# Main.net
KiCad netlist of a schematic drawn in Altium Designer
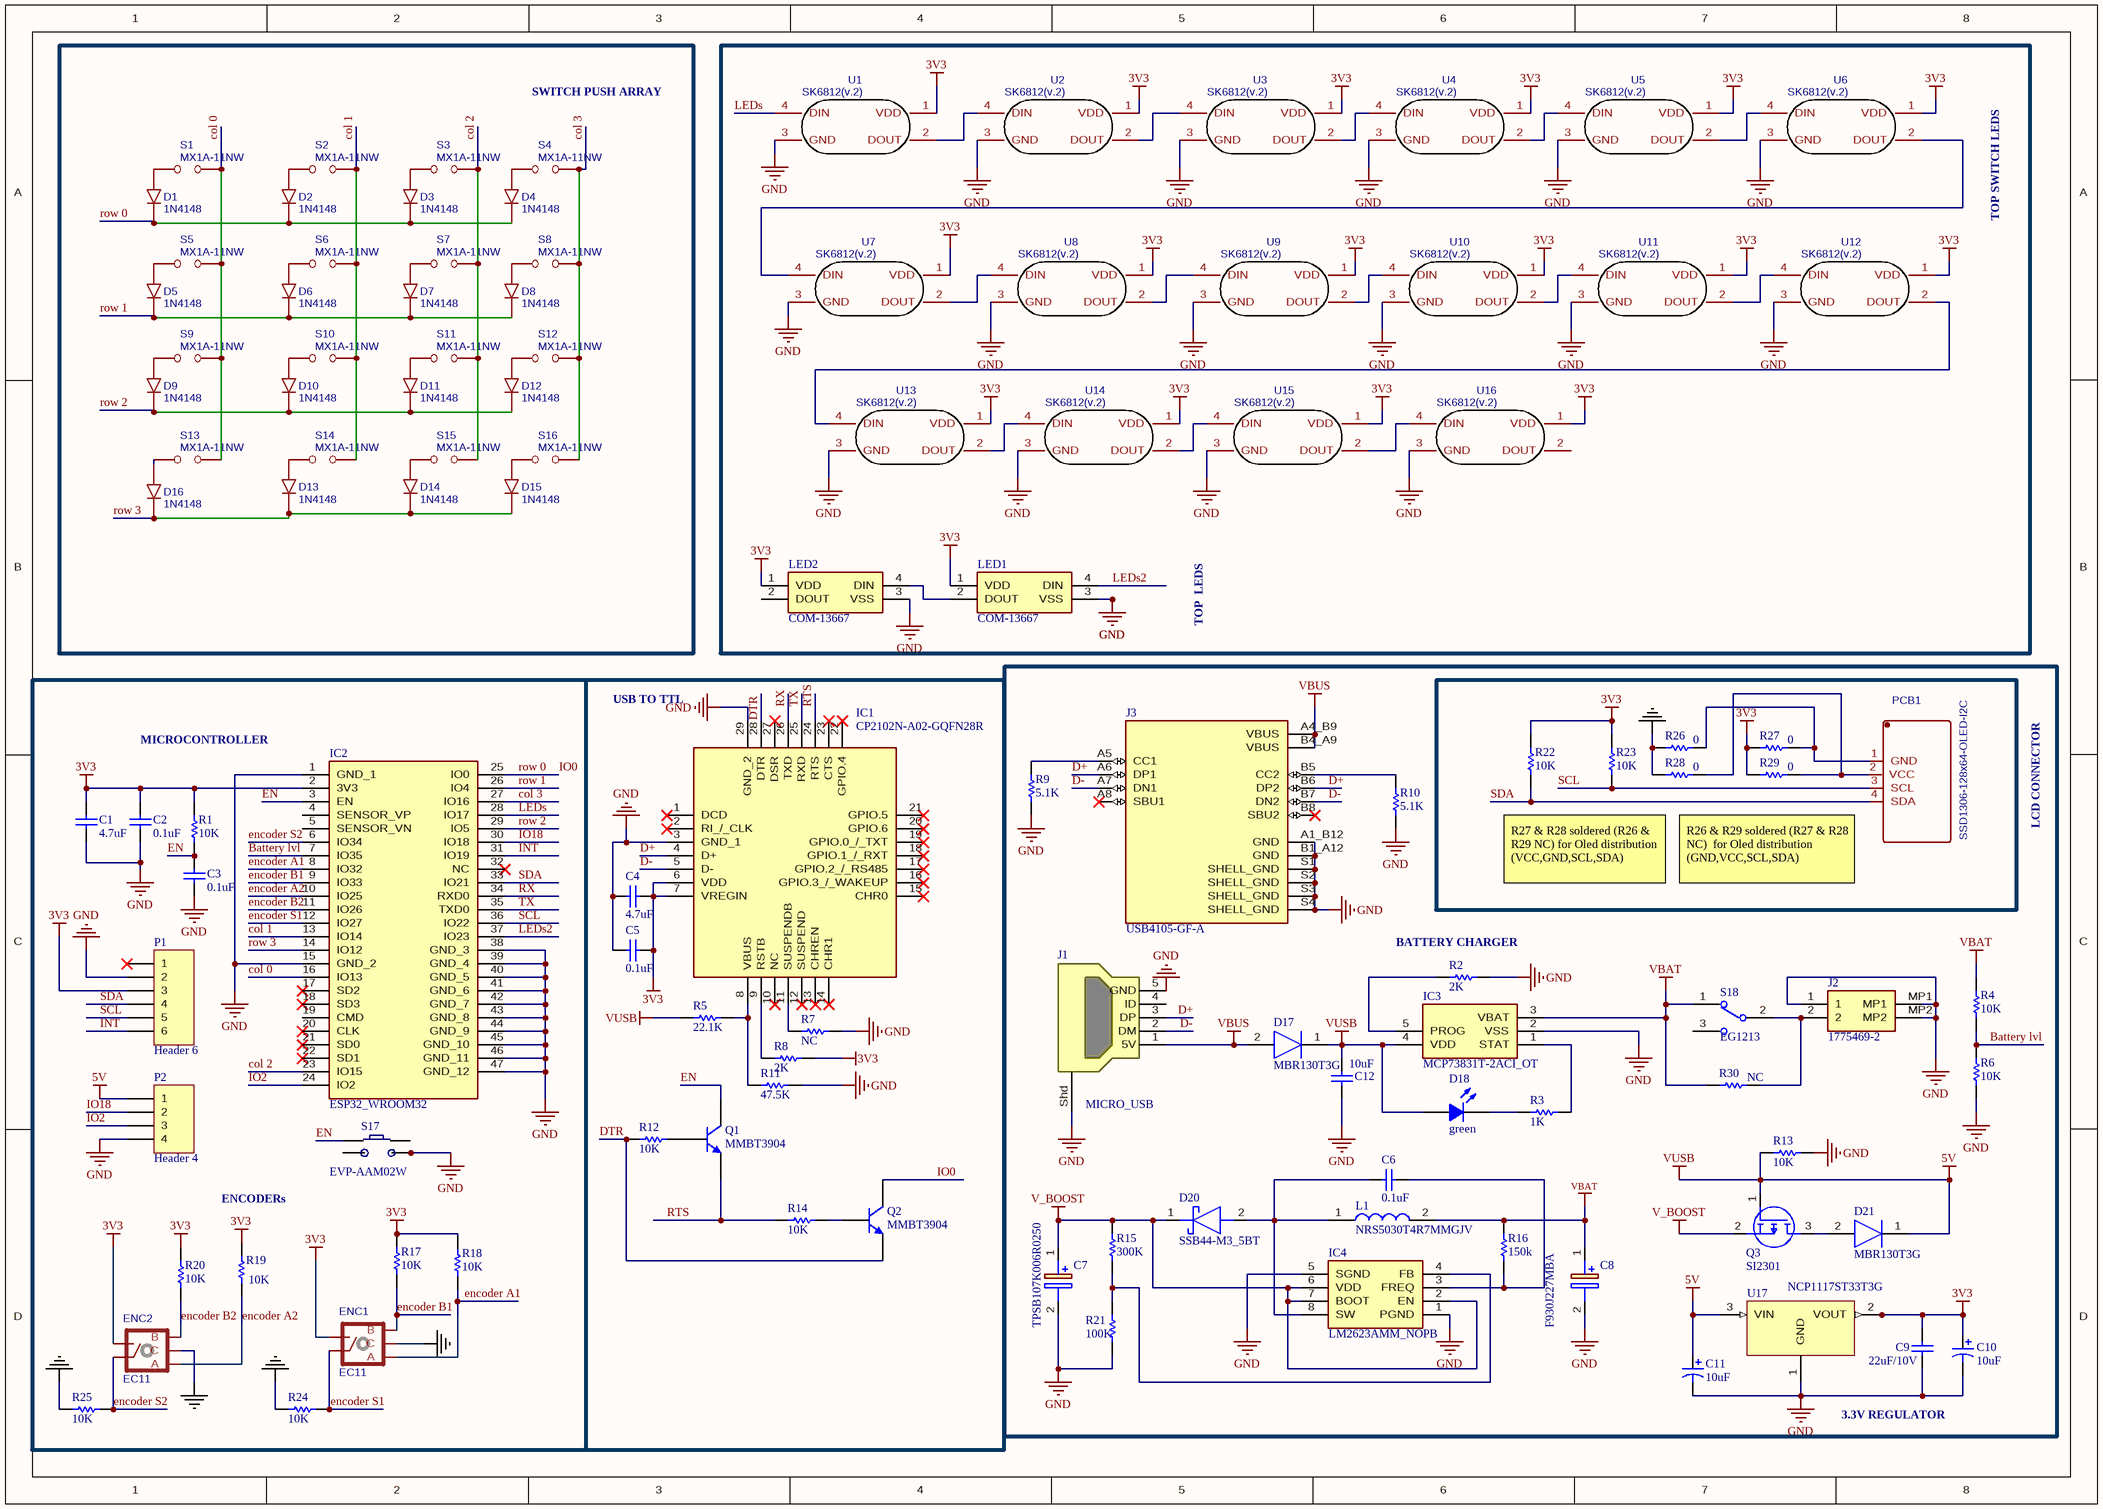
[diagram p0: Main.schdoc]

(export (version "E")
  (design (tool "Eeschema 10.0.6"))
  (components
    (comp (ref "C1") (value "4.7uF") (footprint "C0603_N") (libsource (lib "General") (part "C_SMD")))
    (comp (ref "C2") (value "0.1uF") (footprint "C0603_N") (libsource (lib "General") (part "C_SMD")))
    (comp (ref "C3") (value "0.1uF") (footprint "C0603_N") (libsource (lib "General") (part "C_SMD")))
    (comp (ref "C4") (value "4.7uF") (footprint "C0603_N") (libsource (lib "General") (part "C_SMD")))
    (comp (ref "C5") (value "0.1uF") (footprint "C0603_N") (libsource (lib "General") (part "C_SMD")))
    (comp (ref "C6") (value "0.1uF") (footprint "C0603_N") (libsource (lib "General") (part "C_SMD")))
    (comp (ref "C7")
      (value "TPSB107K006R0250")
      (footprint "CAPPM3528X210N")
      (description "Capacitor Polarised")
      (fields (field (name "MOUSER PART NUMBER") "581-TPSB107K006R0250"))
      (libsource (lib "*") (part "TPSB107K006R0250"))
    )
    (comp (ref "C8")
      (value "F930J227MBA")
      (footprint "CAPPM3528X210N")
      (description "Capacitor Polarised")
      (fields (field (name "MOUSER PART NUMBER") "647-F930J227MBA"))
      (libsource (lib "*") (part "F930J227MBA"))
    )
    (comp (ref "C9") (value "22uF/10V") (footprint "C1206_M") (libsource (lib "General") (part "C_SMD")))
    (comp (ref "C10")
      (value "10uF")
      (footprint "C_TANT_A_3216_N")
      (libsource (lib "General") (part "CP_SMD"))
    )
    (comp (ref "C11")
      (value "10uF")
      (footprint "C_TANT_A_3216_N")
      (libsource (lib "General") (part "CP_SMD"))
    )
    (comp (ref "C12") (value "10uF") (footprint "C0805_N") (libsource (lib "Master") (part "C_SMD")))
    (comp (ref "D1")
      (value "1N4148")
      (footprint "SOD123_N")
      (fields
        (field (name "BOM_MANUFACTURER PART") "1N4148TA")
        (field (name "BOM_SUPPLIER PART") "C124481")
        (field (name "CONTRIBUTOR") "LCSC")
      )
      (libsource (lib "General") (part "1N4148TA"))
    )
    (comp (ref "D2")
      (value "1N4148")
      (footprint "SOD123_N")
      (fields
        (field (name "BOM_MANUFACTURER PART") "1N4148TA")
        (field (name "BOM_SUPPLIER PART") "C124481")
        (field (name "CONTRIBUTOR") "LCSC")
      )
      (libsource (lib "General") (part "1N4148TA"))
    )
    (comp (ref "D3")
      (value "1N4148")
      (footprint "SOD123_N")
      (fields
        (field (name "BOM_MANUFACTURER PART") "1N4148TA")
        (field (name "BOM_SUPPLIER PART") "C124481")
        (field (name "CONTRIBUTOR") "LCSC")
      )
      (libsource (lib "General") (part "1N4148TA"))
    )
    (comp (ref "D4")
      (value "1N4148")
      (footprint "SOD123_N")
      (fields
        (field (name "BOM_MANUFACTURER PART") "1N4148TA")
        (field (name "BOM_SUPPLIER PART") "C124481")
        (field (name "CONTRIBUTOR") "LCSC")
      )
      (libsource (lib "General") (part "1N4148TA"))
    )
    (comp (ref "D5")
      (value "1N4148")
      (footprint "SOD123_N")
      (fields
        (field (name "BOM_MANUFACTURER PART") "1N4148TA")
        (field (name "BOM_SUPPLIER PART") "C124481")
        (field (name "CONTRIBUTOR") "LCSC")
      )
      (libsource (lib "General") (part "1N4148TA"))
    )
    (comp (ref "D6")
      (value "1N4148")
      (footprint "SOD123_N")
      (fields
        (field (name "BOM_MANUFACTURER PART") "1N4148TA")
        (field (name "BOM_SUPPLIER PART") "C124481")
        (field (name "CONTRIBUTOR") "LCSC")
      )
      (libsource (lib "General") (part "1N4148TA"))
    )
    (comp (ref "D7")
      (value "1N4148")
      (footprint "SOD123_N")
      (fields
        (field (name "BOM_MANUFACTURER PART") "1N4148TA")
        (field (name "BOM_SUPPLIER PART") "C124481")
        (field (name "CONTRIBUTOR") "LCSC")
      )
      (libsource (lib "General") (part "1N4148TA"))
    )
    (comp (ref "D8")
      (value "1N4148")
      (footprint "SOD123_N")
      (fields
        (field (name "BOM_MANUFACTURER PART") "1N4148TA")
        (field (name "BOM_SUPPLIER PART") "C124481")
        (field (name "CONTRIBUTOR") "LCSC")
      )
      (libsource (lib "General") (part "1N4148TA"))
    )
    (comp (ref "D9")
      (value "1N4148")
      (footprint "SOD123_N")
      (fields
        (field (name "BOM_MANUFACTURER PART") "1N4148TA")
        (field (name "BOM_SUPPLIER PART") "C124481")
        (field (name "CONTRIBUTOR") "LCSC")
      )
      (libsource (lib "General") (part "1N4148TA"))
    )
    (comp (ref "D10")
      (value "1N4148")
      (footprint "SOD123_N")
      (fields
        (field (name "BOM_MANUFACTURER PART") "1N4148TA")
        (field (name "BOM_SUPPLIER PART") "C124481")
        (field (name "CONTRIBUTOR") "LCSC")
      )
      (libsource (lib "General") (part "1N4148TA"))
    )
    (comp (ref "D11")
      (value "1N4148")
      (footprint "SOD123_N")
      (fields
        (field (name "BOM_MANUFACTURER PART") "1N4148TA")
        (field (name "BOM_SUPPLIER PART") "C124481")
        (field (name "CONTRIBUTOR") "LCSC")
      )
      (libsource (lib "General") (part "1N4148TA"))
    )
    (comp (ref "D12")
      (value "1N4148")
      (footprint "SOD123_N")
      (fields
        (field (name "BOM_MANUFACTURER PART") "1N4148TA")
        (field (name "BOM_SUPPLIER PART") "C124481")
        (field (name "CONTRIBUTOR") "LCSC")
      )
      (libsource (lib "General") (part "1N4148TA"))
    )
    (comp (ref "D13")
      (value "1N4148")
      (footprint "SOD123_N")
      (fields
        (field (name "BOM_MANUFACTURER PART") "1N4148TA")
        (field (name "BOM_SUPPLIER PART") "C124481")
        (field (name "CONTRIBUTOR") "LCSC")
      )
      (libsource (lib "General") (part "1N4148TA"))
    )
    (comp (ref "D14")
      (value "1N4148")
      (footprint "SOD123_N")
      (fields
        (field (name "BOM_MANUFACTURER PART") "1N4148TA")
        (field (name "BOM_SUPPLIER PART") "C124481")
        (field (name "CONTRIBUTOR") "LCSC")
      )
      (libsource (lib "General") (part "1N4148TA"))
    )
    (comp (ref "D15")
      (value "1N4148")
      (footprint "SOD123_N")
      (fields
        (field (name "BOM_MANUFACTURER PART") "1N4148TA")
        (field (name "BOM_SUPPLIER PART") "C124481")
        (field (name "CONTRIBUTOR") "LCSC")
      )
      (libsource (lib "General") (part "1N4148TA"))
    )
    (comp (ref "D16")
      (value "1N4148")
      (footprint "SOD123_N")
      (fields
        (field (name "BOM_MANUFACTURER PART") "1N4148TA")
        (field (name "BOM_SUPPLIER PART") "C124481")
        (field (name "CONTRIBUTOR") "LCSC")
      )
      (libsource (lib "General") (part "1N4148TA"))
    )
    (comp (ref "D17")
      (value "MBR130T3G")
      (footprint "SamacSys:SOD3716X135N")
      (description "Diode")
      (fields (field (name "MOUSER PART NUMBER") "863-MBR130T3G"))
      (libsource (lib "General") (part "MBR130T3G"))
    )
    (comp (ref "D18")
      (value "green")
      (footprint "D0603_L")
      (fields (field (name "COLOR") "green"))
      (libsource (lib "Parquimetro uRAD") (part "LED_SMD"))
    )
    (comp (ref "D20")
      (value "SSB44-M3_5BT")
      (footprint "DIOM5436X244N")
      (description "Schottky Diode")
      (fields
        (field (name "MANUFACTURER_PART_NUMBER") "SSB44-M3/5BT")
        (field (name "MOUSER PART NUMBER") "78-SSB44-M35BT")
      )
      (libsource (lib "*") (part "SSB44-M3_5BT"))
    )
    (comp (ref "D21")
      (value "MBR130T3G")
      (footprint "SamacSys:SOD3716X135N")
      (description "Diode")
      (fields (field (name "MOUSER PART NUMBER") "863-MBR130T3G"))
      (libsource (lib "General") (part "MBR130T3G"))
    )
    (comp (ref "ENC1")
      (value "EC11")
      (footprint "EC11")
      (fields (field (name "BOM_MANUFACTURER PART") "?"))
      (libsource (lib "General") (part "EC11"))
    )
    (comp (ref "ENC2")
      (value "EC11")
      (footprint "EC11")
      (fields (field (name "BOM_MANUFACTURER PART") "?"))
      (libsource (lib "General") (part "EC11"))
    )
    (comp (ref "IC1")
      (value "CP2102N-A02-GQFN28R")
      (footprint "SamacSys:QFN50P500X500X80-29N-D")
      (description "Integrated Circuit")
      (fields (field (name "MOUSER PART NUMBER") "634-CP2102NA02QFN28R"))
      (libsource (lib "General") (part "CP2102N-A02-GQFN28R"))
    )
    (comp (ref "IC2")
      (value "ESP32_WROOM32")
      (footprint "ESP32WROOM32")
      (description "Integrated Circuit")
      (fields (field (name "MANUFACTURER_PART_NUMBER") "ESP32 WROOM32"))
      (libsource (lib "General") (part "ESP32_WROOM32"))
    )
    (comp (ref "IC3")
      (value "MCP73831T-2ACI_OT")
      (footprint "SamacSys:SOT95P270X145-5N")
      (description "Integrated Circuit")
      (fields
        (field (name "MANUFACTURER_PART_NUMBER") "MCP73831T-2ACI/OT")
        (field (name "MOUSER PART NUMBER") "579-MCP73831T-2ACIOT")
      )
      (libsource (lib "*") (part "MCP73831T-2ACI_OT"))
    )
    (comp (ref "IC4")
      (value "LM2623AMM_NOPB")
      (footprint "SOP65P490X110-8N")
      (description "Integrated Circuit")
      (fields
        (field (name "MANUFACTURER_PART_NUMBER") "LM2623AMM/NOPB")
        (field (name "MOUSER PART NUMBER") "926-LM2623AMM/NOPB")
      )
      (libsource (lib "*") (part "LM2623AMM_NOPB"))
    )
    (comp (ref "J1")
      (value "MICRO_USB")
      (footprint "USB MICRO")
      (description "CONN USB MICRO B RECPT SMT R/A")
      (fields (field (name "MANUFACTURER") "FCI") (field (name "MANUFACTURER PART NUMBER") "10118194-0001LF"))
      (libsource (lib "General") (part "MICRO_USB"))
    )
    (comp (ref "J2")
      (value "1775469-2")
      (footprint "17754692")
      (description "Connector")
      (fields (field (name "MOUSER PART NUMBER") "571-1775469-2"))
      (libsource (lib "General") (part "1775469-2"))
    )
    (comp (ref "J3")
      (value "USB4105-GF-A")
      (footprint "USB4105-GF-A:GCT_USB4105-GF-A")
      (fields (field (name "MF") "{'manufacturer': u'GCT'}"))
      (libsource (lib "*") (part "USB4105-GF-A"))
    )
    (comp (ref "L1")
      (value "NRS5030T4R7MMGJV")
      (footprint "NRS5030T4R7MMGJV")
      (description "Inductor")
      (fields (field (name "MOUSER PART NUMBER") "963-NRS5030T4R7MMGJV"))
      (libsource (lib "*") (part "NRS5030T4R7MMGJV"))
    )
    (comp (ref "LED1")
      (value "COM-13667")
      (footprint "COM13667")
      (description "LED")
      (fields (field (name "MOUSER PART NUMBER") "474-COM-13667"))
      (libsource (lib "SamacSys") (part "COM-13667"))
    )
    (comp (ref "LED2")
      (value "COM-13667")
      (footprint "COM13667")
      (description "LED")
      (fields (field (name "MOUSER PART NUMBER") "474-COM-13667"))
      (libsource (lib "SamacSys") (part "COM-13667"))
    )
    (comp (ref "P1")
      (value "Header 6")
      (footprint "HDR1X6")
      (description "Header, 6-Pin")
      (fields (field (name "PUBLISHER") "Altium Limited"))
      (libsource (lib "Miscellaneous Connectors") (part "Header 6"))
    )
    (comp (ref "P2")
      (value "Header 4")
      (footprint "HDR1X4")
      (description "Header, 4-Pin")
      (fields (field (name "PUBLISHER") "Altium Limited"))
      (libsource (lib "General") (part "Header 4"))
    )
    (comp (ref "PCB1")
      (value "SSD1306-128x64-OLED-I2C")
      (footprint "SSD1306_GNDVCC")
      (fields (field (name "BOM_MANUFACTURER PART") "?"))
      (libsource (lib "General") (part "SSD1306-128x64-OLED-I2C"))
    )
    (comp (ref "Q1")
      (value "MMBT3904")
      (footprint "SOT23_N")
      (description "NPN Switching Transistor")
      (fields
        (field (name "MANUFACTURER") "Micro Commercial Co")
        (field (name "MANUFACTURER PART NUMBER") "MMBT3904-TP")
        (field (name "PUBLISHER") "Altium Limited")
      )
      (libsource (lib "General") (part "MMBT3904"))
    )
    (comp (ref "Q2")
      (value "MMBT3904")
      (footprint "SOT23_N")
      (description "NPN Switching Transistor")
      (fields
        (field (name "MANUFACTURER") "Micro Commercial Co")
        (field (name "MANUFACTURER PART NUMBER") "MMBT3904-TP")
        (field (name "PUBLISHER") "Altium Limited")
      )
      (libsource (lib "General") (part "MMBT3904"))
    )
    (comp (ref "Q3")
      (value "SI2301")
      (footprint "SOT95P240X120-3N")
      (description "MOSFET (P-Channel)")
      (libsource (lib "General") (part "SI2301"))
    )
    (comp (ref "R1") (value "10K") (footprint "R0603_N") (libsource (lib "General") (part "R_SMD")))
    (comp (ref "R2") (value "2K") (footprint "R0603_L") (libsource (lib "Parquimetro uRAD") (part "R_SMD")))
    (comp (ref "R3") (value "1K") (footprint "R0603_L") (libsource (lib "Parquimetro uRAD") (part "R_SMD")))
    (comp (ref "R4") (value "10K") (footprint "R0603_N") (libsource (lib "General") (part "R_SMD")))
    (comp (ref "R5") (value "22.1K") (footprint "R0603_N") (libsource (lib "General") (part "R_SMD")))
    (comp (ref "R6") (value "10K") (footprint "R0603_N") (libsource (lib "General") (part "R_SMD")))
    (comp (ref "R7") (value "NC") (footprint "R0603_N") (libsource (lib "General") (part "R_SMD")))
    (comp (ref "R8") (value "2K") (footprint "R0603_N") (libsource (lib "General") (part "R_SMD")))
    (comp (ref "R9") (value "5.1K") (footprint "R0603_N") (libsource (lib "Parquimetro uRAD") (part "R_SMD")))
    (comp (ref "R10")
      (value "5.1K")
      (footprint "R0603_N")
      (libsource (lib "Parquimetro uRAD") (part "R_SMD"))
    )
    (comp (ref "R11") (value "47.5K") (footprint "R0603_N") (libsource (lib "General") (part "R_SMD")))
    (comp (ref "R12") (value "10K") (footprint "R0603_N") (libsource (lib "General") (part "R_SMD")))
    (comp (ref "R13") (value "10K") (footprint "R0603_N") (libsource (lib "General") (part "R_SMD")))
    (comp (ref "R14") (value "10K") (footprint "R0603_N") (libsource (lib "General") (part "R_SMD")))
    (comp (ref "R15") (value "300K") (footprint "R0603_N") (libsource (lib "General") (part "R_SMD")))
    (comp (ref "R16") (value "150k") (footprint "R0603_N") (libsource (lib "General") (part "R_SMD")))
    (comp (ref "R17") (value "10K") (footprint "R0603_N") (libsource (lib "General") (part "R_SMD")))
    (comp (ref "R18") (value "10K") (footprint "R0603_N") (libsource (lib "General") (part "R_SMD")))
    (comp (ref "R19") (value "10K") (footprint "R0603_N") (libsource (lib "General") (part "R_SMD")))
    (comp (ref "R20") (value "10K") (footprint "R0603_N") (libsource (lib "General") (part "R_SMD")))
    (comp (ref "R21") (value "100K") (footprint "R0603_N") (libsource (lib "General") (part "R_SMD")))
    (comp (ref "R22") (value "10K") (footprint "R0603_N") (libsource (lib "General") (part "R_SMD")))
    (comp (ref "R23") (value "10K") (footprint "R0603_N") (libsource (lib "General") (part "R_SMD")))
    (comp (ref "R24") (value "10K") (footprint "R0603_N") (libsource (lib "General") (part "R_SMD")))
    (comp (ref "R25") (value "10K") (footprint "R0603_N") (libsource (lib "General") (part "R_SMD")))
    (comp (ref "R26") (value "0") (footprint "R0402_M") (libsource (lib "General") (part "R_SMD")))
    (comp (ref "R27") (value "0") (footprint "R0402_M") (libsource (lib "General") (part "R_SMD")))
    (comp (ref "R28") (value "0") (footprint "R0402_M") (libsource (lib "General") (part "R_SMD")))
    (comp (ref "R29") (value "0") (footprint "R0402_M") (libsource (lib "General") (part "R_SMD")))
    (comp (ref "R30") (value "NC") (footprint "R0603_N") (libsource (lib "General") (part "R_SMD")))
    (comp (ref "S1")
      (value "MX1A-11NW")
      (footprint "Kailh 1350 socket")
      (fields (field (name "BOM_SUPPLIER PART") "540-MX1A-11NW"))
      (libsource (lib "General") (part "MX1A-11NW"))
    )
    (comp (ref "S2")
      (value "MX1A-11NW")
      (footprint "Kailh 1350 socket")
      (fields (field (name "BOM_SUPPLIER PART") "540-MX1A-11NW"))
      (libsource (lib "General") (part "MX1A-11NW"))
    )
    (comp (ref "S3")
      (value "MX1A-11NW")
      (footprint "Kailh 1350 socket")
      (fields (field (name "BOM_SUPPLIER PART") "540-MX1A-11NW"))
      (libsource (lib "General") (part "MX1A-11NW"))
    )
    (comp (ref "S4")
      (value "MX1A-11NW")
      (footprint "Kailh 1350 socket")
      (fields (field (name "BOM_SUPPLIER PART") "540-MX1A-11NW"))
      (libsource (lib "General") (part "MX1A-11NW"))
    )
    (comp (ref "S5")
      (value "MX1A-11NW")
      (footprint "Kailh 1350 socket")
      (fields (field (name "BOM_SUPPLIER PART") "540-MX1A-11NW"))
      (libsource (lib "General") (part "MX1A-11NW"))
    )
    (comp (ref "S6")
      (value "MX1A-11NW")
      (footprint "Kailh 1350 socket")
      (fields (field (name "BOM_SUPPLIER PART") "540-MX1A-11NW"))
      (libsource (lib "General") (part "MX1A-11NW"))
    )
    (comp (ref "S7")
      (value "MX1A-11NW")
      (footprint "Kailh 1350 socket")
      (fields (field (name "BOM_SUPPLIER PART") "540-MX1A-11NW"))
      (libsource (lib "General") (part "MX1A-11NW"))
    )
    (comp (ref "S8")
      (value "MX1A-11NW")
      (footprint "Kailh 1350 socket")
      (fields (field (name "BOM_SUPPLIER PART") "540-MX1A-11NW"))
      (libsource (lib "General") (part "MX1A-11NW"))
    )
    (comp (ref "S9")
      (value "MX1A-11NW")
      (footprint "Kailh 1350 socket")
      (fields (field (name "BOM_SUPPLIER PART") "540-MX1A-11NW"))
      (libsource (lib "General") (part "MX1A-11NW"))
    )
    (comp (ref "S10")
      (value "MX1A-11NW")
      (footprint "Kailh 1350 socket")
      (fields (field (name "BOM_SUPPLIER PART") "540-MX1A-11NW"))
      (libsource (lib "General") (part "MX1A-11NW"))
    )
    (comp (ref "S11")
      (value "MX1A-11NW")
      (footprint "Kailh 1350 socket")
      (fields (field (name "BOM_SUPPLIER PART") "540-MX1A-11NW"))
      (libsource (lib "General") (part "MX1A-11NW"))
    )
    (comp (ref "S12")
      (value "MX1A-11NW")
      (footprint "Kailh 1350 socket")
      (fields (field (name "BOM_SUPPLIER PART") "540-MX1A-11NW"))
      (libsource (lib "General") (part "MX1A-11NW"))
    )
    (comp (ref "S13")
      (value "MX1A-11NW")
      (footprint "Kailh 1350 socket")
      (fields (field (name "BOM_SUPPLIER PART") "540-MX1A-11NW"))
      (libsource (lib "General") (part "MX1A-11NW"))
    )
    (comp (ref "S14")
      (value "MX1A-11NW")
      (footprint "Kailh 1350 socket")
      (fields (field (name "BOM_SUPPLIER PART") "540-MX1A-11NW"))
      (libsource (lib "General") (part "MX1A-11NW"))
    )
    (comp (ref "S15")
      (value "MX1A-11NW")
      (footprint "Kailh 1350 socket")
      (fields (field (name "BOM_SUPPLIER PART") "540-MX1A-11NW"))
      (libsource (lib "General") (part "MX1A-11NW"))
    )
    (comp (ref "S16")
      (value "MX1A-11NW")
      (footprint "Kailh 1350 socket")
      (fields (field (name "BOM_SUPPLIER PART") "540-MX1A-11NW"))
      (libsource (lib "General") (part "MX1A-11NW"))
    )
    (comp (ref "S17")
      (value "EVP-AAM02W")
      (footprint "EVPAAM02W")
      (description "Switch")
      (fields (field (name "MOUSER PART NUMBER") "667-EVP-AAM02W"))
      (libsource (lib "General") (part "EVP-AAM02W"))
    )
    (comp (ref "S18")
      (value "EG1213")
      (footprint "SK-12D02-VG5")
      (description "<b>EG Series SPDT On-On Right Angle Through Hole Slide Switch</b>")
      (fields (field (name "MF") "{'manufacturer': u'E-Switch'}"))
      (libsource (lib "*") (part "EG1213"))
    )
    (comp (ref "U1")
      (value "SK6812(v.2)")
      (footprint "SK6812MINI-E")
      (fields (field (name "CONTRIBUTOR") "PetrSlachta"))
      (libsource (lib "General") (part "SK6812(v.2)"))
    )
    (comp (ref "U2")
      (value "SK6812(v.2)")
      (footprint "SK6812MINI-E")
      (fields (field (name "CONTRIBUTOR") "PetrSlachta"))
      (libsource (lib "General") (part "SK6812(v.2)"))
    )
    (comp (ref "U3")
      (value "SK6812(v.2)")
      (footprint "SK6812MINI-E")
      (fields (field (name "CONTRIBUTOR") "PetrSlachta"))
      (libsource (lib "General") (part "SK6812(v.2)"))
    )
    (comp (ref "U4")
      (value "SK6812(v.2)")
      (footprint "SK6812MINI-E")
      (fields (field (name "CONTRIBUTOR") "PetrSlachta"))
      (libsource (lib "General") (part "SK6812(v.2)"))
    )
    (comp (ref "U5")
      (value "SK6812(v.2)")
      (footprint "SK6812MINI-E")
      (fields (field (name "CONTRIBUTOR") "PetrSlachta"))
      (libsource (lib "General") (part "SK6812(v.2)"))
    )
    (comp (ref "U6")
      (value "SK6812(v.2)")
      (footprint "SK6812MINI-E")
      (fields (field (name "CONTRIBUTOR") "PetrSlachta"))
      (libsource (lib "General") (part "SK6812(v.2)"))
    )
    (comp (ref "U7")
      (value "SK6812(v.2)")
      (footprint "SK6812MINI-E")
      (fields (field (name "CONTRIBUTOR") "PetrSlachta"))
      (libsource (lib "General") (part "SK6812(v.2)"))
    )
    (comp (ref "U8")
      (value "SK6812(v.2)")
      (footprint "SK6812MINI-E")
      (fields (field (name "CONTRIBUTOR") "PetrSlachta"))
      (libsource (lib "General") (part "SK6812(v.2)"))
    )
    (comp (ref "U9")
      (value "SK6812(v.2)")
      (footprint "SK6812MINI-E")
      (fields (field (name "CONTRIBUTOR") "PetrSlachta"))
      (libsource (lib "General") (part "SK6812(v.2)"))
    )
    (comp (ref "U10")
      (value "SK6812(v.2)")
      (footprint "SK6812MINI-E")
      (fields (field (name "CONTRIBUTOR") "PetrSlachta"))
      (libsource (lib "General") (part "SK6812(v.2)"))
    )
    (comp (ref "U11")
      (value "SK6812(v.2)")
      (footprint "SK6812MINI-E")
      (fields (field (name "CONTRIBUTOR") "PetrSlachta"))
      (libsource (lib "General") (part "SK6812(v.2)"))
    )
    (comp (ref "U12")
      (value "SK6812(v.2)")
      (footprint "SK6812MINI-E")
      (fields (field (name "CONTRIBUTOR") "PetrSlachta"))
      (libsource (lib "General") (part "SK6812(v.2)"))
    )
    (comp (ref "U13")
      (value "SK6812(v.2)")
      (footprint "SK6812MINI-E")
      (fields (field (name "CONTRIBUTOR") "PetrSlachta"))
      (libsource (lib "General") (part "SK6812(v.2)"))
    )
    (comp (ref "U14")
      (value "SK6812(v.2)")
      (footprint "SK6812MINI-E")
      (fields (field (name "CONTRIBUTOR") "PetrSlachta"))
      (libsource (lib "General") (part "SK6812(v.2)"))
    )
    (comp (ref "U15")
      (value "SK6812(v.2)")
      (footprint "SK6812MINI-E")
      (fields (field (name "CONTRIBUTOR") "PetrSlachta"))
      (libsource (lib "General") (part "SK6812(v.2)"))
    )
    (comp (ref "U16")
      (value "SK6812(v.2)")
      (footprint "SK6812MINI-E")
      (fields (field (name "CONTRIBUTOR") "PetrSlachta"))
      (libsource (lib "General") (part "SK6812(v.2)"))
    )
    (comp (ref "U17")
      (value "NCP1117ST33T3G")
      (footprint "SOT-223_M")
      (description "IC REG LINEAR 3.3V 1A SOT223")
      (fields
        (field (name "MANUFACTURER") "ON Semiconductor")
        (field (name "BASE PART NUMBER") "NCP1117ST33")
      )
      (libsource (lib "General") (part "NCP1117ST33T3G"))
    )
  )
  (nets
    (net (code "1") (name "/Battery lvl") (class "Default")
      (node (ref "IC2") (pin "7") (pinfunction "IO35_7") (pintype "passive"))
      (node (ref "R4") (pin "1") (pinfunction "1_1") (pintype "passive"))
      (node (ref "R6") (pin "2") (pinfunction "2_2") (pintype "passive"))
    )
    (net (code "2") (name "/D+") (class "Default")
      (node (ref "IC1") (pin "4") (pinfunction "D+_4") (pintype "passive"))
      (node (ref "J1") (pin "3") (pinfunction "DP_3") (pintype "passive"))
      (node (ref "J3") (pin "A6") (pinfunction "DP1_A6") (pintype "bidirectional"))
      (node (ref "J3") (pin "B6") (pinfunction "DP2_B6") (pintype "bidirectional"))
    )
    (net (code "3") (name "/D-") (class "Default")
      (node (ref "IC1") (pin "5") (pinfunction "D-_5") (pintype "passive"))
      (node (ref "J1") (pin "2") (pinfunction "DM_2") (pintype "passive"))
      (node (ref "J3") (pin "A7") (pinfunction "DN1_A7") (pintype "bidirectional"))
      (node (ref "J3") (pin "B7") (pinfunction "DN2_B7") (pintype "bidirectional"))
    )
    (net (code "4") (name "/DTR") (class "Default")
      (node (ref "IC1") (pin "28") (pinfunction "DTR_28") (pintype "passive"))
      (node (ref "Q2") (pin "2") (pinfunction "E_2") (pintype "passive"))
      (node (ref "R12") (pin "1") (pinfunction "1_1") (pintype "passive"))
    )
    (net (code "5") (name "/EN") (class "Default")
      (node (ref "C3") (pin "2") (pinfunction "2_2") (pintype "passive"))
      (node (ref "IC2") (pin "3") (pinfunction "EN_3") (pintype "passive"))
      (node (ref "Q1") (pin "3") (pinfunction "C_3") (pintype "passive"))
      (node (ref "R1") (pin "1") (pinfunction "1_1") (pintype "passive"))
      (node (ref "S17") (pin "A1") (pinfunction "NO_1_A1") (pintype "passive"))
    )
    (net (code "6") (name "/INT") (class "Default")
      (node (ref "IC2") (pin "31") (pinfunction "IO19_31") (pintype "passive"))
      (node (ref "P1") (pin "6") (pinfunction "6_6") (pintype "passive"))
    )
    (net (code "7") (name "/IO0") (class "Default")
      (node (ref "D1") (pin "2") (pinfunction "2_2") (pintype "passive"))
      (node (ref "D2") (pin "2") (pinfunction "2_2") (pintype "passive"))
      (node (ref "D3") (pin "2") (pinfunction "2_2") (pintype "passive"))
      (node (ref "D4") (pin "2") (pinfunction "2_2") (pintype "passive"))
      (node (ref "IC2") (pin "25") (pinfunction "IO0_25") (pintype "passive"))
      (node (ref "Q2") (pin "3") (pinfunction "C_3") (pintype "passive"))
    )
    (net (code "8") (name "/IO2") (class "Default")
      (node (ref "IC2") (pin "24") (pinfunction "IO2_24") (pintype "passive"))
      (node (ref "P2") (pin "3") (pinfunction "3_3") (pintype "passive"))
    )
    (net (code "9") (name "/IO18") (class "Default")
      (node (ref "IC2") (pin "30") (pinfunction "IO18_30") (pintype "passive"))
      (node (ref "P2") (pin "2") (pinfunction "2_2") (pintype "passive"))
    )
    (net (code "10") (name "/LEDs") (class "Default")
      (node (ref "IC2") (pin "28") (pinfunction "IO17_28") (pintype "passive"))
      (node (ref "U1") (pin "4") (pinfunction "DIN_4") (pintype "passive"))
    )
    (net (code "11") (name "/LEDs2") (class "Default")
      (node (ref "IC2") (pin "37") (pinfunction "IO23_37") (pintype "passive"))
      (node (ref "LED1") (pin "4") (pinfunction "DIN_4") (pintype "passive"))
    )
    (net (code "12") (name "/RTS") (class "Default")
      (node (ref "IC1") (pin "24") (pinfunction "RTS_24") (pintype "passive"))
      (node (ref "Q1") (pin "2") (pinfunction "E_2") (pintype "passive"))
      (node (ref "R14") (pin "2") (pinfunction "2_2") (pintype "passive"))
    )
    (net (code "13") (name "/RX") (class "Default")
      (node (ref "IC1") (pin "26") (pinfunction "TXD_26") (pintype "passive"))
      (node (ref "IC2") (pin "34") (pinfunction "RXD0_34") (pintype "passive"))
    )
    (net (code "14") (name "/SCL") (class "Default")
      (node (ref "IC2") (pin "36") (pinfunction "IO22_36") (pintype "passive"))
      (node (ref "P1") (pin "5") (pinfunction "5_5") (pintype "passive"))
      (node (ref "PCB1") (pin "3") (pinfunction "SCL_3") (pintype "passive"))
      (node (ref "R23") (pin "1") (pinfunction "1_1") (pintype "passive"))
    )
    (net (code "15") (name "/SDA") (class "Default")
      (node (ref "IC2") (pin "33") (pinfunction "IO21_33") (pintype "passive"))
      (node (ref "P1") (pin "4") (pinfunction "4_4") (pintype "passive"))
      (node (ref "PCB1") (pin "4") (pinfunction "SDA_4") (pintype "passive"))
      (node (ref "R22") (pin "1") (pinfunction "1_1") (pintype "passive"))
    )
    (net (code "16") (name "/TX") (class "Default")
      (node (ref "IC1") (pin "25") (pinfunction "RXD_25") (pintype "passive"))
      (node (ref "IC2") (pin "35") (pinfunction "TXD0_35") (pintype "passive"))
    )
    (net (code "17") (name "/col 0") (class "Default")
      (node (ref "IC2") (pin "16") (pinfunction "IO13_16") (pintype "passive"))
      (node (ref "S1") (pin "2") (pinfunction "2_2") (pintype "passive"))
      (node (ref "S13") (pin "2") (pinfunction "2_2") (pintype "passive"))
      (node (ref "S5") (pin "2") (pinfunction "2_2") (pintype "passive"))
      (node (ref "S9") (pin "2") (pinfunction "2_2") (pintype "passive"))
    )
    (net (code "18") (name "/col 1") (class "Default")
      (node (ref "IC2") (pin "13") (pinfunction "IO14_13") (pintype "passive"))
      (node (ref "S10") (pin "2") (pinfunction "2_2") (pintype "passive"))
      (node (ref "S14") (pin "2") (pinfunction "2_2") (pintype "passive"))
      (node (ref "S2") (pin "2") (pinfunction "2_2") (pintype "passive"))
      (node (ref "S6") (pin "2") (pinfunction "2_2") (pintype "passive"))
    )
    (net (code "19") (name "/col 2") (class "Default")
      (node (ref "IC2") (pin "23") (pinfunction "IO15_23") (pintype "passive"))
      (node (ref "S11") (pin "2") (pinfunction "2_2") (pintype "passive"))
      (node (ref "S15") (pin "2") (pinfunction "2_2") (pintype "passive"))
      (node (ref "S3") (pin "2") (pinfunction "2_2") (pintype "passive"))
      (node (ref "S7") (pin "2") (pinfunction "2_2") (pintype "passive"))
    )
    (net (code "20") (name "/col 3") (class "Default")
      (node (ref "IC2") (pin "27") (pinfunction "IO16_27") (pintype "passive"))
      (node (ref "S12") (pin "2") (pinfunction "2_2") (pintype "passive"))
      (node (ref "S16") (pin "2") (pinfunction "2_2") (pintype "passive"))
      (node (ref "S4") (pin "2") (pinfunction "2_2") (pintype "passive"))
      (node (ref "S8") (pin "2") (pinfunction "2_2") (pintype "passive"))
    )
    (net (code "21") (name "/encoder A1") (class "Default")
      (node (ref "ENC1") (pin "3") (pinfunction "A_3") (pintype "passive"))
      (node (ref "IC2") (pin "8") (pinfunction "IO32_8") (pintype "passive"))
      (node (ref "R18") (pin "1") (pinfunction "1_1") (pintype "passive"))
    )
    (net (code "22") (name "/encoder A2") (class "Default")
      (node (ref "ENC2") (pin "3") (pinfunction "A_3") (pintype "passive"))
      (node (ref "IC2") (pin "10") (pinfunction "IO25_10") (pintype "passive"))
      (node (ref "R19") (pin "1") (pinfunction "1_1") (pintype "passive"))
    )
    (net (code "23") (name "/encoder B1") (class "Default")
      (node (ref "ENC1") (pin "4") (pinfunction "B_4") (pintype "passive"))
      (node (ref "IC2") (pin "9") (pinfunction "IO33_9") (pintype "passive"))
      (node (ref "R17") (pin "1") (pinfunction "1_1") (pintype "passive"))
    )
    (net (code "24") (name "/encoder B2") (class "Default")
      (node (ref "ENC2") (pin "4") (pinfunction "B_4") (pintype "passive"))
      (node (ref "IC2") (pin "11") (pinfunction "IO26_11") (pintype "passive"))
      (node (ref "R20") (pin "1") (pinfunction "1_1") (pintype "passive"))
    )
    (net (code "25") (name "/encoder S1") (class "Default")
      (node (ref "ENC1") (pin "1") (pinfunction "1_1") (pintype "passive"))
      (node (ref "IC2") (pin "12") (pinfunction "IO27_12") (pintype "passive"))
      (node (ref "R24") (pin "1") (pinfunction "1_1") (pintype "passive"))
    )
    (net (code "26") (name "/encoder S2") (class "Default")
      (node (ref "ENC2") (pin "1") (pinfunction "1_1") (pintype "passive"))
      (node (ref "IC2") (pin "6") (pinfunction "IO34_6") (pintype "passive"))
      (node (ref "R25") (pin "1") (pinfunction "1_1") (pintype "passive"))
    )
    (net (code "27") (name "/row 1") (class "Default")
      (node (ref "D5") (pin "2") (pinfunction "2_2") (pintype "passive"))
      (node (ref "D6") (pin "2") (pinfunction "2_2") (pintype "passive"))
      (node (ref "D7") (pin "2") (pinfunction "2_2") (pintype "passive"))
      (node (ref "D8") (pin "2") (pinfunction "2_2") (pintype "passive"))
      (node (ref "IC2") (pin "26") (pinfunction "IO4_26") (pintype "passive"))
    )
    (net (code "28") (name "/row 2") (class "Default")
      (node (ref "D10") (pin "2") (pinfunction "2_2") (pintype "passive"))
      (node (ref "D11") (pin "2") (pinfunction "2_2") (pintype "passive"))
      (node (ref "D12") (pin "2") (pinfunction "2_2") (pintype "passive"))
      (node (ref "D9") (pin "2") (pinfunction "2_2") (pintype "passive"))
      (node (ref "IC2") (pin "29") (pinfunction "IO5_29") (pintype "passive"))
    )
    (net (code "29") (name "/row 3") (class "Default")
      (node (ref "D13") (pin "2") (pinfunction "2_2") (pintype "passive"))
      (node (ref "D14") (pin "2") (pinfunction "2_2") (pintype "passive"))
      (node (ref "D15") (pin "2") (pinfunction "2_2") (pintype "passive"))
      (node (ref "D16") (pin "2") (pinfunction "2_2") (pintype "passive"))
      (node (ref "IC2") (pin "14") (pinfunction "IO12_14") (pintype "passive"))
    )
    (net (code "30") (name "3V3") (class "Default")
      (node (ref "C1") (pin "2") (pinfunction "2_2") (pintype "passive"))
      (node (ref "C10") (pin "1") (pinfunction "1_1") (pintype "passive"))
      (node (ref "C2") (pin "2") (pinfunction "2_2") (pintype "passive"))
      (node (ref "C4") (pin "1") (pinfunction "1_1") (pintype "passive"))
      (node (ref "C5") (pin "1") (pinfunction "1_1") (pintype "passive"))
      (node (ref "C9") (pin "2") (pinfunction "2_2") (pintype "passive"))
      (node (ref "ENC1") (pin "2") (pinfunction "2_2") (pintype "passive"))
      (node (ref "ENC2") (pin "2") (pinfunction "2_2") (pintype "passive"))
      (node (ref "IC1") (pin "6") (pinfunction "VDD_6") (pintype "passive"))
      (node (ref "IC1") (pin "7") (pinfunction "VREGIN_7") (pintype "passive"))
      (node (ref "IC2") (pin "2") (pinfunction "3V3_2") (pintype "passive"))
      (node (ref "LED1") (pin "1") (pinfunction "VDD_1") (pintype "passive"))
      (node (ref "LED2") (pin "1") (pinfunction "VDD_1") (pintype "passive"))
      (node (ref "P1") (pin "3") (pinfunction "3_3") (pintype "passive"))
      (node (ref "R1") (pin "2") (pinfunction "2_2") (pintype "passive"))
      (node (ref "R17") (pin "2") (pinfunction "2_2") (pintype "passive"))
      (node (ref "R18") (pin "2") (pinfunction "2_2") (pintype "passive"))
      (node (ref "R19") (pin "2") (pinfunction "2_2") (pintype "passive"))
      (node (ref "R20") (pin "2") (pinfunction "2_2") (pintype "passive"))
      (node (ref "R22") (pin "2") (pinfunction "2_2") (pintype "passive"))
      (node (ref "R23") (pin "2") (pinfunction "2_2") (pintype "passive"))
      (node (ref "R27") (pin "2") (pinfunction "2_2") (pintype "passive"))
      (node (ref "R29") (pin "2") (pinfunction "2_2") (pintype "passive"))
      (node (ref "R8") (pin "1") (pinfunction "1_1") (pintype "passive"))
      (node (ref "U1") (pin "1") (pinfunction "VDD_1") (pintype "passive"))
      (node (ref "U10") (pin "1") (pinfunction "VDD_1") (pintype "passive"))
      (node (ref "U11") (pin "1") (pinfunction "VDD_1") (pintype "passive"))
      (node (ref "U12") (pin "1") (pinfunction "VDD_1") (pintype "passive"))
      (node (ref "U13") (pin "1") (pinfunction "VDD_1") (pintype "passive"))
      (node (ref "U14") (pin "1") (pinfunction "VDD_1") (pintype "passive"))
      (node (ref "U15") (pin "1") (pinfunction "VDD_1") (pintype "passive"))
      (node (ref "U16") (pin "1") (pinfunction "VDD_1") (pintype "passive"))
      (node (ref "U17") (pin "2") (pinfunction "VOUT_2") (pintype "output"))
      (node (ref "U17") (pin "4") (pinfunction "VOUT_4") (pintype "output"))
      (node (ref "U2") (pin "1") (pinfunction "VDD_1") (pintype "passive"))
      (node (ref "U3") (pin "1") (pinfunction "VDD_1") (pintype "passive"))
      (node (ref "U4") (pin "1") (pinfunction "VDD_1") (pintype "passive"))
      (node (ref "U5") (pin "1") (pinfunction "VDD_1") (pintype "passive"))
      (node (ref "U6") (pin "1") (pinfunction "VDD_1") (pintype "passive"))
      (node (ref "U7") (pin "1") (pinfunction "VDD_1") (pintype "passive"))
      (node (ref "U8") (pin "1") (pinfunction "VDD_1") (pintype "passive"))
      (node (ref "U9") (pin "1") (pinfunction "VDD_1") (pintype "passive"))
    )
    (net (code "31") (name "5V") (class "Default")
      (node (ref "C11") (pin "1") (pinfunction "1_1") (pintype "passive"))
      (node (ref "C12") (pin "2") (pinfunction "2_2") (pintype "passive"))
      (node (ref "D17") (pin "1") (pinfunction "K_1") (pintype "passive"))
      (node (ref "D18") (pin "2") (pinfunction "A_2") (pintype "passive"))
      (node (ref "D21") (pin "1") (pinfunction "K_1") (pintype "passive"))
      (node (ref "IC3") (pin "4") (pinfunction "VDD_4") (pintype "passive"))
      (node (ref "P2") (pin "1") (pinfunction "1_1") (pintype "passive"))
      (node (ref "Q3") (pin "1") (pinfunction "G_1") (pintype "passive"))
      (node (ref "R13") (pin "1") (pinfunction "1_1") (pintype "passive"))
      (node (ref "R5") (pin "1") (pinfunction "1_1") (pintype "passive"))
      (node (ref "U17") (pin "3") (pinfunction "VIN_3") (pintype "input"))
    )
    (net (code "32") (name "GND") (class "Default")
      (node (ref "C1") (pin "1") (pinfunction "1_1") (pintype "passive"))
      (node (ref "C10") (pin "2") (pinfunction "2_2") (pintype "passive"))
      (node (ref "C11") (pin "2") (pinfunction "2_2") (pintype "passive"))
      (node (ref "C12") (pin "1") (pinfunction "1_1") (pintype "passive"))
      (node (ref "C2") (pin "1") (pinfunction "1_1") (pintype "passive"))
      (node (ref "C3") (pin "1") (pinfunction "1_1") (pintype "passive"))
      (node (ref "C4") (pin "2") (pinfunction "2_2") (pintype "passive"))
      (node (ref "C5") (pin "2") (pinfunction "2_2") (pintype "passive"))
      (node (ref "C7") (pin "2") (pinfunction "-_2") (pintype "passive"))
      (node (ref "C8") (pin "2") (pinfunction "-_2") (pintype "passive"))
      (node (ref "C9") (pin "1") (pinfunction "1_1") (pintype "passive"))
      (node (ref "ENC1") (pin "5") (pinfunction "C_5") (pintype "passive"))
      (node (ref "ENC2") (pin "5") (pinfunction "C_5") (pintype "passive"))
      (node (ref "IC1") (pin "29") (pinfunction "GND_2_29") (pintype "passive"))
      (node (ref "IC1") (pin "3") (pinfunction "GND_1_3") (pintype "passive"))
      (node (ref "IC2") (pin "1") (pinfunction "GND_1_1") (pintype "passive"))
      (node (ref "IC2") (pin "15") (pinfunction "GND_2_15") (pintype "passive"))
      (node (ref "IC2") (pin "38") (pinfunction "GND_3_38") (pintype "passive"))
      (node (ref "IC2") (pin "39") (pinfunction "GND_4_39") (pintype "passive"))
      (node (ref "IC2") (pin "40") (pinfunction "GND_5_40") (pintype "passive"))
      (node (ref "IC2") (pin "41") (pinfunction "GND_6_41") (pintype "passive"))
      (node (ref "IC2") (pin "42") (pinfunction "GND_7_42") (pintype "passive"))
      (node (ref "IC2") (pin "43") (pinfunction "GND_8_43") (pintype "passive"))
      (node (ref "IC2") (pin "44") (pinfunction "GND_9_44") (pintype "passive"))
      (node (ref "IC2") (pin "45") (pinfunction "GND_10_45") (pintype "passive"))
      (node (ref "IC2") (pin "46") (pinfunction "GND_11_46") (pintype "passive"))
      (node (ref "IC2") (pin "47") (pinfunction "GND_12_47") (pintype "passive"))
      (node (ref "IC3") (pin "2") (pinfunction "VSS_2") (pintype "passive"))
      (node (ref "IC4") (pin "1") (pinfunction "PGND_1") (pintype "passive"))
      (node (ref "IC4") (pin "5") (pinfunction "SGND_5") (pintype "passive"))
      (node (ref "J1") (pin "5") (pinfunction "GND_5") (pintype "power_in"))
      (node (ref "J1") (pin "Shd") (pinfunction "6_Shd") (pintype "passive"))
      (node (ref "J2") (pin "1") (pinfunction "1_1") (pintype "passive"))
      (node (ref "J2") (pin "MP1") (pinfunction "MP1_MP1") (pintype "passive"))
      (node (ref "J2") (pin "MP2") (pinfunction "MP2_MP2") (pintype "passive"))
      (node (ref "J3") (pin "A1_B12") (pinfunction "GND_A1_B12") (pintype "power_in"))
      (node (ref "J3") (pin "B1_A12") (pinfunction "GND_B1_A12") (pintype "power_in"))
      (node (ref "J3") (pin "S1") (pinfunction "SHELL_GND_S1") (pintype "power_in"))
      (node (ref "J3") (pin "S2") (pinfunction "SHELL_GND_S2") (pintype "power_in"))
      (node (ref "J3") (pin "S3") (pinfunction "SHELL_GND_S3") (pintype "power_in"))
      (node (ref "J3") (pin "S4") (pinfunction "SHELL_GND_S4") (pintype "power_in"))
      (node (ref "LED1") (pin "3") (pinfunction "VSS_3") (pintype "passive"))
      (node (ref "LED2") (pin "3") (pinfunction "VSS_3") (pintype "passive"))
      (node (ref "P1") (pin "2") (pinfunction "2_2") (pintype "passive"))
      (node (ref "P2") (pin "4") (pinfunction "4_4") (pintype "passive"))
      (node (ref "R10") (pin "1") (pinfunction "1_1") (pintype "passive"))
      (node (ref "R11") (pin "1") (pinfunction "1_1") (pintype "passive"))
      (node (ref "R13") (pin "2") (pinfunction "2_2") (pintype "passive"))
      (node (ref "R2") (pin "1") (pinfunction "1_1") (pintype "passive"))
      (node (ref "R21") (pin "1") (pinfunction "1_1") (pintype "passive"))
      (node (ref "R24") (pin "2") (pinfunction "2_2") (pintype "passive"))
      (node (ref "R25") (pin "2") (pinfunction "2_2") (pintype "passive"))
      (node (ref "R26") (pin "2") (pinfunction "2_2") (pintype "passive"))
      (node (ref "R28") (pin "2") (pinfunction "2_2") (pintype "passive"))
      (node (ref "R6") (pin "1") (pinfunction "1_1") (pintype "passive"))
      (node (ref "R7") (pin "1") (pinfunction "1_1") (pintype "passive"))
      (node (ref "R9") (pin "1") (pinfunction "1_1") (pintype "passive"))
      (node (ref "S17") (pin "B2") (pinfunction "COM_2_B2") (pintype "passive"))
      (node (ref "U1") (pin "3") (pinfunction "GND_3") (pintype "passive"))
      (node (ref "U10") (pin "3") (pinfunction "GND_3") (pintype "passive"))
      (node (ref "U11") (pin "3") (pinfunction "GND_3") (pintype "passive"))
      (node (ref "U12") (pin "3") (pinfunction "GND_3") (pintype "passive"))
      (node (ref "U13") (pin "3") (pinfunction "GND_3") (pintype "passive"))
      (node (ref "U14") (pin "3") (pinfunction "GND_3") (pintype "passive"))
      (node (ref "U15") (pin "3") (pinfunction "GND_3") (pintype "passive"))
      (node (ref "U16") (pin "3") (pinfunction "GND_3") (pintype "passive"))
      (node (ref "U17") (pin "1") (pinfunction "GND_1") (pintype "power_in"))
      (node (ref "U2") (pin "3") (pinfunction "GND_3") (pintype "passive"))
      (node (ref "U3") (pin "3") (pinfunction "GND_3") (pintype "passive"))
      (node (ref "U4") (pin "3") (pinfunction "GND_3") (pintype "passive"))
      (node (ref "U5") (pin "3") (pinfunction "GND_3") (pintype "passive"))
      (node (ref "U6") (pin "3") (pinfunction "GND_3") (pintype "passive"))
      (node (ref "U7") (pin "3") (pinfunction "GND_3") (pintype "passive"))
      (node (ref "U8") (pin "3") (pinfunction "GND_3") (pintype "passive"))
      (node (ref "U9") (pin "3") (pinfunction "GND_3") (pintype "passive"))
    )
    (net (code "33") (name "Net-(D1-Pad1)") (class "Default")
      (node (ref "D1") (pin "1") (pinfunction "1_1") (pintype "passive"))
      (node (ref "S1") (pin "1") (pinfunction "1_1") (pintype "passive"))
    )
    (net (code "34") (name "Net-(D2-Pad1)") (class "Default")
      (node (ref "D2") (pin "1") (pinfunction "1_1") (pintype "passive"))
      (node (ref "S2") (pin "1") (pinfunction "1_1") (pintype "passive"))
    )
    (net (code "35") (name "Net-(D3-Pad1)") (class "Default")
      (node (ref "D3") (pin "1") (pinfunction "1_1") (pintype "passive"))
      (node (ref "S3") (pin "1") (pinfunction "1_1") (pintype "passive"))
    )
    (net (code "36") (name "Net-(D4-Pad1)") (class "Default")
      (node (ref "D4") (pin "1") (pinfunction "1_1") (pintype "passive"))
      (node (ref "S4") (pin "1") (pinfunction "1_1") (pintype "passive"))
    )
    (net (code "37") (name "Net-(D5-Pad1)") (class "Default")
      (node (ref "D5") (pin "1") (pinfunction "1_1") (pintype "passive"))
      (node (ref "S5") (pin "1") (pinfunction "1_1") (pintype "passive"))
    )
    (net (code "38") (name "Net-(D6-Pad1)") (class "Default")
      (node (ref "D6") (pin "1") (pinfunction "1_1") (pintype "passive"))
      (node (ref "S6") (pin "1") (pinfunction "1_1") (pintype "passive"))
    )
    (net (code "39") (name "Net-(D7-Pad1)") (class "Default")
      (node (ref "D7") (pin "1") (pinfunction "1_1") (pintype "passive"))
      (node (ref "S7") (pin "1") (pinfunction "1_1") (pintype "passive"))
    )
    (net (code "40") (name "Net-(D8-Pad1)") (class "Default")
      (node (ref "D8") (pin "1") (pinfunction "1_1") (pintype "passive"))
      (node (ref "S8") (pin "1") (pinfunction "1_1") (pintype "passive"))
    )
    (net (code "41") (name "Net-(D9-Pad1)") (class "Default")
      (node (ref "D9") (pin "1") (pinfunction "1_1") (pintype "passive"))
      (node (ref "S9") (pin "1") (pinfunction "1_1") (pintype "passive"))
    )
    (net (code "42") (name "Net-(D10-Pad1)") (class "Default")
      (node (ref "D10") (pin "1") (pinfunction "1_1") (pintype "passive"))
      (node (ref "S10") (pin "1") (pinfunction "1_1") (pintype "passive"))
    )
    (net (code "43") (name "Net-(D11-Pad1)") (class "Default")
      (node (ref "D11") (pin "1") (pinfunction "1_1") (pintype "passive"))
      (node (ref "S11") (pin "1") (pinfunction "1_1") (pintype "passive"))
    )
    (net (code "44") (name "Net-(D12-Pad1)") (class "Default")
      (node (ref "D12") (pin "1") (pinfunction "1_1") (pintype "passive"))
      (node (ref "S12") (pin "1") (pinfunction "1_1") (pintype "passive"))
    )
    (net (code "45") (name "Net-(D13-Pad1)") (class "Default")
      (node (ref "D13") (pin "1") (pinfunction "1_1") (pintype "passive"))
      (node (ref "S14") (pin "1") (pinfunction "1_1") (pintype "passive"))
    )
    (net (code "46") (name "Net-(D14-Pad1)") (class "Default")
      (node (ref "D14") (pin "1") (pinfunction "1_1") (pintype "passive"))
      (node (ref "S15") (pin "1") (pinfunction "1_1") (pintype "passive"))
    )
    (net (code "47") (name "Net-(D15-Pad1)") (class "Default")
      (node (ref "D15") (pin "1") (pinfunction "1_1") (pintype "passive"))
      (node (ref "S16") (pin "1") (pinfunction "1_1") (pintype "passive"))
    )
    (net (code "48") (name "Net-(D16-Pad1)") (class "Default")
      (node (ref "D16") (pin "1") (pinfunction "1_1") (pintype "passive"))
      (node (ref "S13") (pin "1") (pinfunction "1_1") (pintype "passive"))
    )
    (net (code "49") (name "Net-(D18-K)") (class "Default")
      (node (ref "D18") (pin "1") (pinfunction "K_1") (pintype "passive"))
      (node (ref "R3") (pin "2") (pinfunction "2_2") (pintype "passive"))
    )
    (net (code "50") (name "Net-(D20-A)") (class "Default")
      (node (ref "C6") (pin "1") (pinfunction "1_1") (pintype "passive"))
      (node (ref "D20") (pin "2") (pinfunction "A_2") (pintype "passive"))
      (node (ref "IC4") (pin "8") (pinfunction "SW_8") (pintype "passive"))
      (node (ref "L1") (pin "1") (pinfunction "1_1") (pintype "passive"))
    )
    (net (code "51") (name "Net-(D21-A)") (class "Default")
      (node (ref "D21") (pin "2") (pinfunction "A_2") (pintype "passive"))
      (node (ref "Q3") (pin "3") (pinfunction "D_3") (pintype "passive"))
    )
    (net (code "52") (name "Net-(IC1-RSTB)") (class "Default")
      (node (ref "IC1") (pin "9") (pinfunction "RSTB_9") (pintype "passive"))
      (node (ref "R8") (pin "2") (pinfunction "2_2") (pintype "passive"))
    )
    (net (code "53") (name "Net-(IC1-SUSPENDB)") (class "Default")
      (node (ref "IC1") (pin "11") (pinfunction "SUSPENDB_11") (pintype "passive"))
      (node (ref "R7") (pin "2") (pinfunction "2_2") (pintype "passive"))
    )
    (net (code "54") (name "Net-(IC1-VBUS)") (class "Default")
      (node (ref "IC1") (pin "8") (pinfunction "VBUS_8") (pintype "passive"))
      (node (ref "R11") (pin "2") (pinfunction "2_2") (pintype "passive"))
      (node (ref "R5") (pin "2") (pinfunction "2_2") (pintype "passive"))
    )
    (net (code "55") (name "Net-(IC3-PROG)") (class "Default")
      (node (ref "IC3") (pin "5") (pinfunction "PROG_5") (pintype "passive"))
      (node (ref "R2") (pin "2") (pinfunction "2_2") (pintype "passive"))
    )
    (net (code "56") (name "Net-(IC3-STAT)") (class "Default")
      (node (ref "IC3") (pin "1") (pinfunction "STAT_1") (pintype "passive"))
      (node (ref "R3") (pin "1") (pinfunction "1_1") (pintype "passive"))
    )
    (net (code "57") (name "Net-(IC4-FB)") (class "Default")
      (node (ref "IC4") (pin "4") (pinfunction "FB_4") (pintype "passive"))
      (node (ref "R15") (pin "1") (pinfunction "1_1") (pintype "passive"))
      (node (ref "R21") (pin "2") (pinfunction "2_2") (pintype "passive"))
    )
    (net (code "58") (name "Net-(IC4-FREQ)") (class "Default")
      (node (ref "C6") (pin "2") (pinfunction "2_2") (pintype "passive"))
      (node (ref "IC4") (pin "3") (pinfunction "FREQ_3") (pintype "passive"))
      (node (ref "R16") (pin "1") (pinfunction "1_1") (pintype "passive"))
    )
    (net (code "59") (name "Net-(J2-Pad2)") (class "Default")
      (node (ref "J2") (pin "2") (pinfunction "2_2") (pintype "passive"))
      (node (ref "R30") (pin "1") (pinfunction "1_1") (pintype "passive"))
      (node (ref "S18") (pin "2") (pinfunction "2_2") (pintype "passive"))
    )
    (net (code "60") (name "Net-(J3-CC1)") (class "Default")
      (node (ref "J3") (pin "A5") (pinfunction "CC1_A5") (pintype "bidirectional"))
      (node (ref "R9") (pin "2") (pinfunction "2_2") (pintype "passive"))
    )
    (net (code "61") (name "Net-(J3-CC2)") (class "Default")
      (node (ref "J3") (pin "B5") (pinfunction "CC2_B5") (pintype "bidirectional"))
      (node (ref "R10") (pin "2") (pinfunction "2_2") (pintype "passive"))
    )
    (net (code "62") (name "Net-(LED1-DOUT)") (class "Default")
      (node (ref "LED1") (pin "2") (pinfunction "DOUT_2") (pintype "passive"))
      (node (ref "LED2") (pin "4") (pinfunction "DIN_4") (pintype "passive"))
    )
    (net (code "63") (name "Net-(PCB1-GND)") (class "Default")
      (node (ref "PCB1") (pin "1") (pinfunction "GND_1") (pintype "passive"))
      (node (ref "R26") (pin "1") (pinfunction "1_1") (pintype "passive"))
      (node (ref "R27") (pin "1") (pinfunction "1_1") (pintype "passive"))
    )
    (net (code "64") (name "Net-(PCB1-VCC)") (class "Default")
      (node (ref "PCB1") (pin "2") (pinfunction "VCC_2") (pintype "passive"))
      (node (ref "R28") (pin "1") (pinfunction "1_1") (pintype "passive"))
      (node (ref "R29") (pin "1") (pinfunction "1_1") (pintype "passive"))
    )
    (net (code "65") (name "Net-(Q1-B)") (class "Default")
      (node (ref "Q1") (pin "1") (pinfunction "B_1") (pintype "passive"))
      (node (ref "R12") (pin "2") (pinfunction "2_2") (pintype "passive"))
    )
    (net (code "66") (name "Net-(Q2-B)") (class "Default")
      (node (ref "Q2") (pin "1") (pinfunction "B_1") (pintype "passive"))
      (node (ref "R14") (pin "1") (pinfunction "1_1") (pintype "passive"))
    )
    (net (code "67") (name "Net-(U1-DOUT)") (class "Default")
      (node (ref "U1") (pin "2") (pinfunction "DOUT_2") (pintype "passive"))
      (node (ref "U2") (pin "4") (pinfunction "DIN_4") (pintype "passive"))
    )
    (net (code "68") (name "Net-(U2-DOUT)") (class "Default")
      (node (ref "U2") (pin "2") (pinfunction "DOUT_2") (pintype "passive"))
      (node (ref "U3") (pin "4") (pinfunction "DIN_4") (pintype "passive"))
    )
    (net (code "69") (name "Net-(U3-DOUT)") (class "Default")
      (node (ref "U3") (pin "2") (pinfunction "DOUT_2") (pintype "passive"))
      (node (ref "U4") (pin "4") (pinfunction "DIN_4") (pintype "passive"))
    )
    (net (code "70") (name "Net-(U4-DOUT)") (class "Default")
      (node (ref "U4") (pin "2") (pinfunction "DOUT_2") (pintype "passive"))
      (node (ref "U5") (pin "4") (pinfunction "DIN_4") (pintype "passive"))
    )
    (net (code "71") (name "Net-(U5-DOUT)") (class "Default")
      (node (ref "U5") (pin "2") (pinfunction "DOUT_2") (pintype "passive"))
      (node (ref "U6") (pin "4") (pinfunction "DIN_4") (pintype "passive"))
    )
    (net (code "72") (name "Net-(U6-DOUT)") (class "Default")
      (node (ref "U6") (pin "2") (pinfunction "DOUT_2") (pintype "passive"))
      (node (ref "U7") (pin "4") (pinfunction "DIN_4") (pintype "passive"))
    )
    (net (code "73") (name "Net-(U7-DOUT)") (class "Default")
      (node (ref "U7") (pin "2") (pinfunction "DOUT_2") (pintype "passive"))
      (node (ref "U8") (pin "4") (pinfunction "DIN_4") (pintype "passive"))
    )
    (net (code "74") (name "Net-(U8-DOUT)") (class "Default")
      (node (ref "U8") (pin "2") (pinfunction "DOUT_2") (pintype "passive"))
      (node (ref "U9") (pin "4") (pinfunction "DIN_4") (pintype "passive"))
    )
    (net (code "75") (name "Net-(U10-DIN)") (class "Default")
      (node (ref "U10") (pin "4") (pinfunction "DIN_4") (pintype "passive"))
      (node (ref "U9") (pin "2") (pinfunction "DOUT_2") (pintype "passive"))
    )
    (net (code "76") (name "Net-(U10-DOUT)") (class "Default")
      (node (ref "U10") (pin "2") (pinfunction "DOUT_2") (pintype "passive"))
      (node (ref "U11") (pin "4") (pinfunction "DIN_4") (pintype "passive"))
    )
    (net (code "77") (name "Net-(U11-DOUT)") (class "Default")
      (node (ref "U11") (pin "2") (pinfunction "DOUT_2") (pintype "passive"))
      (node (ref "U12") (pin "4") (pinfunction "DIN_4") (pintype "passive"))
    )
    (net (code "78") (name "Net-(U12-DOUT)") (class "Default")
      (node (ref "U12") (pin "2") (pinfunction "DOUT_2") (pintype "passive"))
      (node (ref "U13") (pin "4") (pinfunction "DIN_4") (pintype "passive"))
    )
    (net (code "79") (name "Net-(U13-DOUT)") (class "Default")
      (node (ref "U13") (pin "2") (pinfunction "DOUT_2") (pintype "passive"))
      (node (ref "U14") (pin "4") (pinfunction "DIN_4") (pintype "passive"))
    )
    (net (code "80") (name "Net-(U14-DOUT)") (class "Default")
      (node (ref "U14") (pin "2") (pinfunction "DOUT_2") (pintype "passive"))
      (node (ref "U15") (pin "4") (pinfunction "DIN_4") (pintype "passive"))
    )
    (net (code "81") (name "Net-(U15-DOUT)") (class "Default")
      (node (ref "U15") (pin "2") (pinfunction "DOUT_2") (pintype "passive"))
      (node (ref "U16") (pin "4") (pinfunction "DIN_4") (pintype "passive"))
    )
    (net (code "82") (name "VBAT") (class "Default")
      (node (ref "C8") (pin "1") (pinfunction "+_1") (pintype "passive"))
      (node (ref "IC3") (pin "3") (pinfunction "VBAT_3") (pintype "passive"))
      (node (ref "L1") (pin "2") (pinfunction "2_2") (pintype "passive"))
      (node (ref "R16") (pin "2") (pinfunction "2_2") (pintype "passive"))
      (node (ref "R30") (pin "2") (pinfunction "2_2") (pintype "passive"))
      (node (ref "R4") (pin "2") (pinfunction "2_2") (pintype "passive"))
      (node (ref "S18") (pin "1") (pinfunction "1_1") (pintype "passive"))
    )
    (net (code "83") (name "VBUS") (class "Default")
      (node (ref "D17") (pin "2") (pinfunction "A_2") (pintype "passive"))
      (node (ref "J1") (pin "1") (pinfunction "5V_1") (pintype "power_in"))
      (node (ref "J3") (pin "A4_B9") (pinfunction "VBUS_A4_B9") (pintype "power_in"))
      (node (ref "J3") (pin "B4_A9") (pinfunction "VBUS_B4_A9") (pintype "power_in"))
    )
    (net (code "84") (name "V_BOOST") (class "Default")
      (node (ref "C7") (pin "1") (pinfunction "+_1") (pintype "passive"))
      (node (ref "D20") (pin "1") (pinfunction "K_1") (pintype "passive"))
      (node (ref "IC4") (pin "2") (pinfunction "EN_2") (pintype "passive"))
      (node (ref "IC4") (pin "6") (pinfunction "VDD_6") (pintype "passive"))
      (node (ref "IC4") (pin "7") (pinfunction "BOOT_7") (pintype "passive"))
      (node (ref "Q3") (pin "2") (pinfunction "S_2") (pintype "passive"))
      (node (ref "R15") (pin "2") (pinfunction "2_2") (pintype "passive"))
    )
    (net (code "85") (name "unconnected-(IC1-CHR0-Pad15)") (class "Default")
      (node (ref "IC1") (pin "15") (pinfunction "CHR0_15") (pintype "passive+no_connect"))
    )
    (net (code "86") (name "unconnected-(IC1-CHR1-Pad14)") (class "Default")
      (node (ref "IC1") (pin "14") (pinfunction "CHR1_14") (pintype "passive+no_connect"))
    )
    (net (code "87") (name "unconnected-(IC1-CHREN-Pad13)") (class "Default")
      (node (ref "IC1") (pin "13") (pinfunction "CHREN_13") (pintype "passive+no_connect"))
    )
    (net (code "88") (name "unconnected-(IC1-CTS-Pad23)") (class "Default")
      (node (ref "IC1") (pin "23") (pinfunction "CTS_23") (pintype "passive+no_connect"))
    )
    (net (code "89") (name "unconnected-(IC1-DCD-Pad1)") (class "Default")
      (node (ref "IC1") (pin "1") (pinfunction "DCD_1") (pintype "passive+no_connect"))
    )
    (net (code "90") (name "unconnected-(IC1-DSR-Pad27)") (class "Default")
      (node (ref "IC1") (pin "27") (pinfunction "DSR_27") (pintype "passive+no_connect"))
    )
    (net (code "91") (name "unconnected-(IC1-GPIO.0_{slash}_TXT-Pad19)") (class "Default")
      (node (ref "IC1") (pin "19") (pinfunction "GPIO.0_/_TXT_19") (pintype "passive+no_connect"))
    )
    (net (code "92") (name "unconnected-(IC1-GPIO.1_{slash}_RXT-Pad18)") (class "Default")
      (node (ref "IC1") (pin "18") (pinfunction "GPIO.1_/_RXT_18") (pintype "passive+no_connect"))
    )
    (net (code "93") (name "unconnected-(IC1-GPIO.2_{slash}_RS485-Pad17)") (class "Default")
      (node (ref "IC1") (pin "17") (pinfunction "GPIO.2_/_RS485_17") (pintype "passive+no_connect"))
    )
    (net (code "94") (name "unconnected-(IC1-GPIO.3_{slash}_WAKEUP-Pad16)") (class "Default")
      (node (ref "IC1") (pin "16") (pinfunction "GPIO.3_/_WAKEUP_16") (pintype "passive+no_connect"))
    )
    (net (code "95") (name "unconnected-(IC1-GPIO.4-Pad22)") (class "Default")
      (node (ref "IC1") (pin "22") (pinfunction "GPIO.4_22") (pintype "passive+no_connect"))
    )
    (net (code "96") (name "unconnected-(IC1-GPIO.5-Pad21)") (class "Default")
      (node (ref "IC1") (pin "21") (pinfunction "GPIO.5_21") (pintype "passive+no_connect"))
    )
    (net (code "97") (name "unconnected-(IC1-GPIO.6-Pad20)") (class "Default")
      (node (ref "IC1") (pin "20") (pinfunction "GPIO.6_20") (pintype "passive+no_connect"))
    )
    (net (code "98") (name "unconnected-(IC1-NC-Pad10)") (class "Default")
      (node (ref "IC1") (pin "10") (pinfunction "NC_10") (pintype "passive+no_connect"))
    )
    (net (code "99") (name "unconnected-(IC1-RI_{slash}_CLK-Pad2)") (class "Default")
      (node (ref "IC1") (pin "2") (pinfunction "RI_/_CLK_2") (pintype "passive+no_connect"))
    )
    (net (code "100") (name "unconnected-(IC1-SUSPEND-Pad12)") (class "Default")
      (node (ref "IC1") (pin "12") (pinfunction "SUSPEND_12") (pintype "passive+no_connect"))
    )
    (net (code "101") (name "unconnected-(IC2-CLK-Pad20)") (class "Default")
      (node (ref "IC2") (pin "20") (pinfunction "CLK_20") (pintype "passive+no_connect"))
    )
    (net (code "102") (name "unconnected-(IC2-CMD-Pad19)") (class "Default")
      (node (ref "IC2") (pin "19") (pinfunction "CMD_19") (pintype "passive"))
    )
    (net (code "103") (name "unconnected-(IC2-NC-Pad32)") (class "Default")
      (node (ref "IC2") (pin "32") (pinfunction "NC_32") (pintype "passive+no_connect"))
    )
    (net (code "104") (name "unconnected-(IC2-SD0-Pad21)") (class "Default")
      (node (ref "IC2") (pin "21") (pinfunction "SD0_21") (pintype "passive+no_connect"))
    )
    (net (code "105") (name "unconnected-(IC2-SD1-Pad22)") (class "Default")
      (node (ref "IC2") (pin "22") (pinfunction "SD1_22") (pintype "passive+no_connect"))
    )
    (net (code "106") (name "unconnected-(IC2-SD2-Pad17)") (class "Default")
      (node (ref "IC2") (pin "17") (pinfunction "SD2_17") (pintype "passive+no_connect"))
    )
    (net (code "107") (name "unconnected-(IC2-SD3-Pad18)") (class "Default")
      (node (ref "IC2") (pin "18") (pinfunction "SD3_18") (pintype "passive+no_connect"))
    )
    (net (code "108") (name "unconnected-(IC2-SENSOR_VN-Pad5)") (class "Default")
      (node (ref "IC2") (pin "5") (pinfunction "SENSOR_VN_5") (pintype "passive"))
    )
    (net (code "109") (name "unconnected-(IC2-SENSOR_VP-Pad4)") (class "Default")
      (node (ref "IC2") (pin "4") (pinfunction "SENSOR_VP_4") (pintype "passive"))
    )
    (net (code "110") (name "unconnected-(J1-ID-Pad4)") (class "Default")
      (node (ref "J1") (pin "4") (pinfunction "ID_4") (pintype "passive"))
    )
    (net (code "111") (name "unconnected-(J3-SBU1-PadA8)") (class "Default")
      (node (ref "J3") (pin "A8") (pinfunction "SBU1_A8") (pintype "bidirectional+no_connect"))
    )
    (net (code "112") (name "unconnected-(J3-SBU2-PadB8)") (class "Default")
      (node (ref "J3") (pin "B8") (pinfunction "SBU2_B8") (pintype "bidirectional+no_connect"))
    )
    (net (code "113") (name "unconnected-(LED2-DOUT-Pad2)") (class "Default")
      (node (ref "LED2") (pin "2") (pinfunction "DOUT_2") (pintype "passive"))
    )
    (net (code "114") (name "unconnected-(P1-Pad1)") (class "Default")
      (node (ref "P1") (pin "1") (pinfunction "1_1") (pintype "passive+no_connect"))
    )
    (net (code "115") (name "unconnected-(S17-COM_1-PadA2)") (class "Default")
      (node (ref "S17") (pin "A2") (pinfunction "COM_1_A2") (pintype "passive"))
    )
    (net (code "116") (name "unconnected-(S17-NO_2-PadB1)") (class "Default")
      (node (ref "S17") (pin "B1") (pinfunction "NO_2_B1") (pintype "passive"))
    )
    (net (code "117") (name "unconnected-(S18-Pad3)") (class "Default")
      (node (ref "S18") (pin "3") (pinfunction "3_3") (pintype "passive"))
    )
    (net (code "118") (name "unconnected-(U16-DOUT-Pad2)") (class "Default")
      (node (ref "U16") (pin "2") (pinfunction "DOUT_2") (pintype "passive"))
    )
  )
)
